# LED_Driver_and_Switch_Breakout.net
KiCad netlist of a schematic drawn in Altium Designer
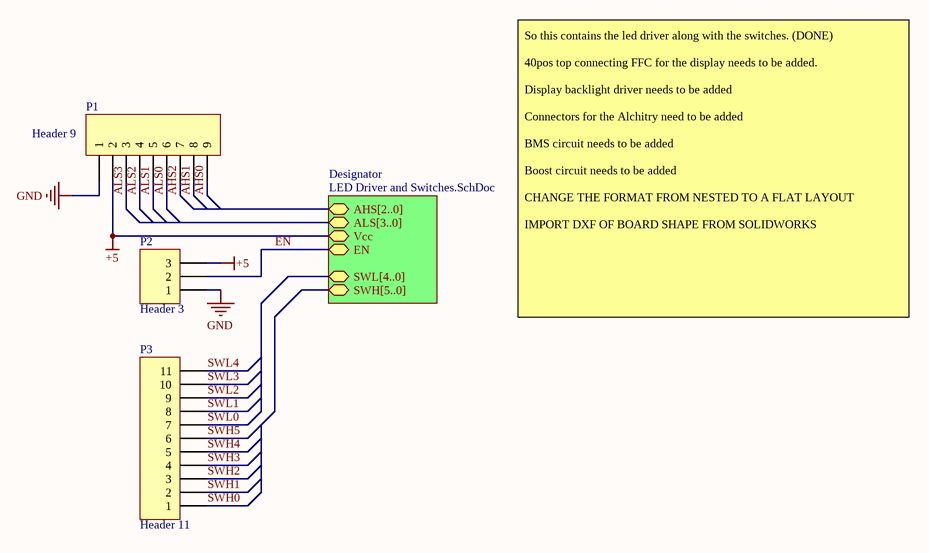
[diagram p0: LED Driver and Switch Breakout.SchDoc]

(export (version "E")
  (design (tool "Eeschema 10.0.6"))
  (components
    (comp (ref "P1")
      (value "Header 9")
      (footprint "HDR1X9")
      (description "Header, 9-Pin")
      (fields (field (name "PUBLISHER") "Altium Limited"))
      (libsource (lib "Miscellaneous Connectors") (part "Header 9"))
    )
    (comp (ref "P2")
      (value "Header 3")
      (footprint "HDR1X3")
      (description "Header, 3-Pin")
      (fields (field (name "PUBLISHER") "Altium Limited"))
      (libsource (lib "Miscellaneous Connectors") (part "Header 3"))
    )
    (comp (ref "P3")
      (value "Header 11")
      (footprint "HDR1X11")
      (description "Header, 11-Pin")
      (fields (field (name "PUBLISHER") "Altium Limited"))
      (libsource (lib "Miscellaneous Connectors") (part "Header 11"))
    )
  )
  (nets
    (net (code "1") (name "+5") (class "Default")
      (node (ref "P1") (pin "2") (pinfunction "2_2") (pintype "passive"))
      (node (ref "P2") (pin "3") (pinfunction "3_3") (pintype "passive"))
    )
    (net (code "2") (name "/AHS0") (class "Default")
      (node (ref "P1") (pin "9") (pinfunction "9_9") (pintype "passive"))
    )
    (net (code "3") (name "/AHS1") (class "Default")
      (node (ref "P1") (pin "8") (pinfunction "8_8") (pintype "passive"))
    )
    (net (code "4") (name "/AHS2") (class "Default")
      (node (ref "P1") (pin "7") (pinfunction "7_7") (pintype "passive"))
    )
    (net (code "6") (name "/ALS0") (class "Default")
      (node (ref "P1") (pin "6") (pinfunction "6_6") (pintype "passive"))
    )
    (net (code "7") (name "/ALS1") (class "Default")
      (node (ref "P1") (pin "5") (pinfunction "5_5") (pintype "passive"))
    )
    (net (code "8") (name "/ALS2") (class "Default")
      (node (ref "P1") (pin "4") (pinfunction "4_4") (pintype "passive"))
    )
    (net (code "9") (name "/ALS3") (class "Default")
      (node (ref "P1") (pin "3") (pinfunction "3_3") (pintype "passive"))
    )
    (net (code "11") (name "/EN") (class "Default")
      (node (ref "P2") (pin "2") (pinfunction "2_2") (pintype "passive"))
    )
    (net (code "12") (name "/SWH0") (class "Default")
      (node (ref "P3") (pin "1") (pinfunction "1_1") (pintype "passive"))
    )
    (net (code "13") (name "/SWH1") (class "Default")
      (node (ref "P3") (pin "2") (pinfunction "2_2") (pintype "passive"))
    )
    (net (code "14") (name "/SWH2") (class "Default")
      (node (ref "P3") (pin "3") (pinfunction "3_3") (pintype "passive"))
    )
    (net (code "15") (name "/SWH3") (class "Default")
      (node (ref "P3") (pin "4") (pinfunction "4_4") (pintype "passive"))
    )
    (net (code "16") (name "/SWH4") (class "Default")
      (node (ref "P3") (pin "5") (pinfunction "5_5") (pintype "passive"))
    )
    (net (code "17") (name "/SWH5") (class "Default")
      (node (ref "P3") (pin "6") (pinfunction "6_6") (pintype "passive"))
    )
    (net (code "19") (name "/SWL0") (class "Default")
      (node (ref "P3") (pin "7") (pinfunction "7_7") (pintype "passive"))
    )
    (net (code "20") (name "/SWL1") (class "Default")
      (node (ref "P3") (pin "8") (pinfunction "8_8") (pintype "passive"))
    )
    (net (code "21") (name "/SWL2") (class "Default")
      (node (ref "P3") (pin "9") (pinfunction "9_9") (pintype "passive"))
    )
    (net (code "22") (name "/SWL3") (class "Default")
      (node (ref "P3") (pin "10") (pinfunction "10_10") (pintype "passive"))
    )
    (net (code "23") (name "/SWL4") (class "Default")
      (node (ref "P3") (pin "11") (pinfunction "11_11") (pintype "passive"))
    )
    (net (code "25") (name "GND") (class "Default")
      (node (ref "P1") (pin "1") (pinfunction "1_1") (pintype "passive"))
      (node (ref "P2") (pin "1") (pinfunction "1_1") (pintype "passive"))
    )
  )
)
